# freqdivider.net
KiCad netlist of a schematic drawn in EAGLE
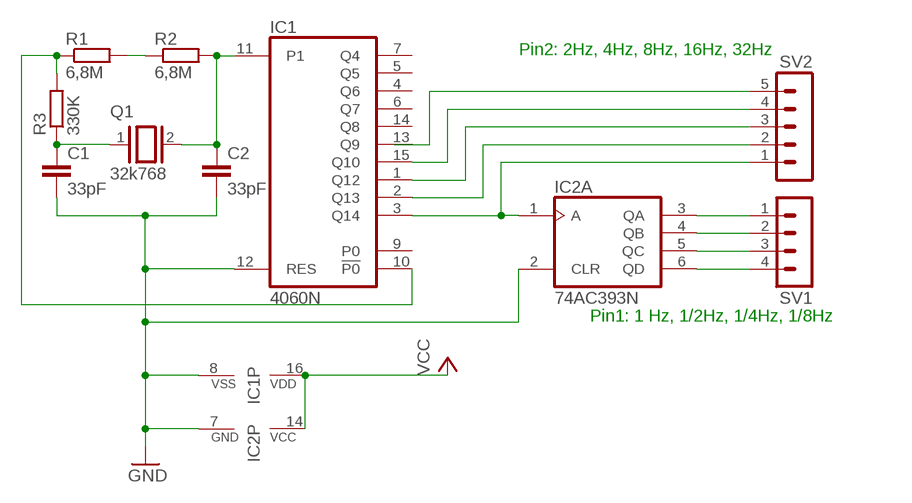
[diagram p0: schematic, sheet 1]

(export (version "E")
  (design (tool "Eeschema 10.0.6"))
  (components
    (comp (ref "C1")
      (value "33pF")
      (footprint "eagle-import:C025-060X050")
      (libsource (lib "eagle-import") (part "C-EU025-060X050"))
    )
    (comp (ref "C2")
      (value "33pF")
      (footprint "eagle-import:C025-060X050")
      (libsource (lib "eagle-import") (part "C-EU025-060X050"))
    )
    (comp (ref "IC1")
      (value "4060N")
      (footprint "eagle-import:DIL16")
      (libsource (lib "eagle-import") (part "4060N"))
    )
    (comp (ref "IC2")
      (value "74AC393N")
      (footprint "eagle-import:DIL14")
      (libsource (lib "eagle-import") (part "74393NAC"))
    )
    (comp (ref "Q1")
      (value "32k768")
      (footprint "eagle-import:Q")
      (libsource (lib "eagle-import") (part "XTAL"))
    )
    (comp (ref "R1")
      (value "6,8M")
      (footprint "eagle-import:0207_10")
      (libsource (lib "eagle-import") (part "R-EU_0207/10"))
    )
    (comp (ref "R2")
      (value "6,8M")
      (footprint "eagle-import:0207_10")
      (libsource (lib "eagle-import") (part "R-EU_0207/10"))
    )
    (comp (ref "R3")
      (value "330K")
      (footprint "eagle-import:0207_10")
      (libsource (lib "eagle-import") (part "R-EU_0207/10"))
    )
    (comp (ref "SV1")
      (value "MA04-1")
      (footprint "eagle-import:MA04-1")
      (libsource (lib "eagle-import") (part "MA04-1"))
    )
    (comp (ref "SV2")
      (value "MA05-1")
      (footprint "eagle-import:MA05-1")
      (libsource (lib "eagle-import") (part "MA05-1"))
    )
  )
  (nets
    (net (code "1") (name "GND") (class "Default")
      (node (ref "C1") (pin "2") (pinfunction "2_2") (pintype "passive"))
      (node (ref "C2") (pin "2") (pinfunction "2_2") (pintype "passive"))
      (node (ref "IC1") (pin "12") (pinfunction "RES_12") (pintype "input"))
      (node (ref "IC1") (pin "8") (pinfunction "VSS_8") (pintype "power_in"))
      (node (ref "IC2") (pin "2") (pinfunction "CLR_2") (pintype "input"))
      (node (ref "IC2") (pin "7") (pinfunction "GND_7") (pintype "power_in"))
    )
    (net (code "2") (name "Net-(C1-Pad1)") (class "Default")
      (node (ref "C1") (pin "1") (pinfunction "1_1") (pintype "passive"))
      (node (ref "Q1") (pin "1") (pinfunction "1_1") (pintype "passive"))
      (node (ref "R3") (pin "1") (pinfunction "1_1") (pintype "passive"))
    )
    (net (code "3") (name "Net-(IC1A-P1)") (class "Default")
      (node (ref "C2") (pin "1") (pinfunction "1_1") (pintype "passive"))
      (node (ref "IC1") (pin "11") (pinfunction "P1_11") (pintype "input"))
      (node (ref "Q1") (pin "2") (pinfunction "2_2") (pintype "passive"))
      (node (ref "R2") (pin "2") (pinfunction "2_2") (pintype "passive"))
    )
    (net (code "4") (name "Net-(IC1A-Q10)") (class "Default")
      (node (ref "IC1") (pin "15") (pinfunction "Q10_15") (pintype "output"))
      (node (ref "SV2") (pin "4") (pinfunction "4_4") (pintype "passive"))
    )
    (net (code "5") (name "Net-(IC1A-Q12)") (class "Default")
      (node (ref "IC1") (pin "1") (pinfunction "Q12_1") (pintype "output"))
      (node (ref "SV2") (pin "3") (pinfunction "3_3") (pintype "passive"))
    )
    (net (code "6") (name "Net-(IC1A-Q13)") (class "Default")
      (node (ref "IC1") (pin "2") (pinfunction "Q13_2") (pintype "output"))
      (node (ref "SV2") (pin "2") (pinfunction "2_2") (pintype "passive"))
    )
    (net (code "7") (name "Net-(IC1A-Q14)") (class "Default")
      (node (ref "IC1") (pin "3") (pinfunction "Q14_3") (pintype "output"))
      (node (ref "IC2") (pin "1") (pinfunction "A_1") (pintype "input"))
      (node (ref "SV2") (pin "1") (pinfunction "1_1") (pintype "passive"))
    )
    (net (code "8") (name "Net-(IC1A-~{P0})") (class "Default")
      (node (ref "IC1") (pin "10") (pinfunction "~{P0}_10") (pintype "output"))
      (node (ref "R1") (pin "1") (pinfunction "1_1") (pintype "passive"))
      (node (ref "R3") (pin "2") (pinfunction "2_2") (pintype "passive"))
    )
    (net (code "9") (name "Net-(IC2A-QA)") (class "Default")
      (node (ref "IC2") (pin "3") (pinfunction "QA_3") (pintype "output"))
      (node (ref "SV1") (pin "1") (pinfunction "1_1") (pintype "passive"))
    )
    (net (code "10") (name "Net-(IC2A-QB)") (class "Default")
      (node (ref "IC2") (pin "4") (pinfunction "QB_4") (pintype "output"))
      (node (ref "SV1") (pin "2") (pinfunction "2_2") (pintype "passive"))
    )
    (net (code "11") (name "Net-(IC2A-QC)") (class "Default")
      (node (ref "IC2") (pin "5") (pinfunction "QC_5") (pintype "output"))
      (node (ref "SV1") (pin "3") (pinfunction "3_3") (pintype "passive"))
    )
    (net (code "12") (name "Net-(IC2A-QD)") (class "Default")
      (node (ref "IC2") (pin "6") (pinfunction "QD_6") (pintype "output"))
      (node (ref "SV1") (pin "4") (pinfunction "4_4") (pintype "passive"))
    )
    (net (code "13") (name "Net-(R1-Pad2)") (class "Default")
      (node (ref "R1") (pin "2") (pinfunction "2_2") (pintype "passive"))
      (node (ref "R2") (pin "1") (pinfunction "1_1") (pintype "passive"))
    )
    (net (code "14") (name "VCC") (class "Default")
      (node (ref "IC1") (pin "16") (pinfunction "VDD_16") (pintype "power_in"))
      (node (ref "IC2") (pin "14") (pinfunction "VCC_14") (pintype "power_in"))
    )
    (net (code "15") (name "unconnected-(IC1A-P0-Pad9)") (class "Default")
      (node (ref "IC1") (pin "9") (pinfunction "P0_9") (pintype "output"))
    )
    (net (code "16") (name "unconnected-(IC1A-Q4-Pad7)") (class "Default")
      (node (ref "IC1") (pin "7") (pinfunction "Q4_7") (pintype "output"))
    )
    (net (code "17") (name "unconnected-(IC1A-Q5-Pad5)") (class "Default")
      (node (ref "IC1") (pin "5") (pinfunction "Q5_5") (pintype "output"))
    )
    (net (code "18") (name "unconnected-(IC1A-Q6-Pad4)") (class "Default")
      (node (ref "IC1") (pin "4") (pinfunction "Q6_4") (pintype "output"))
    )
    (net (code "19") (name "unconnected-(IC1A-Q7-Pad6)") (class "Default")
      (node (ref "IC1") (pin "6") (pinfunction "Q7_6") (pintype "output"))
    )
    (net (code "20") (name "unconnected-(IC1A-Q8-Pad14)") (class "Default")
      (node (ref "IC1") (pin "14") (pinfunction "Q8_14") (pintype "output"))
    )
    (net (code "21") (name "unconnected-(IC1A-Q9-Pad13)") (class "Default")
      (node (ref "IC1") (pin "13") (pinfunction "Q9_13") (pintype "output"))
    )
    (net (code "22") (name "unconnected-(SV2-Pad5)") (class "Default")
      (node (ref "SV2") (pin "5") (pinfunction "5_5") (pintype "passive"))
    )
  )
)
